# 7segement4digits1badidea-many-digits-mk-.net
KiCad netlist of a schematic drawn in EAGLE
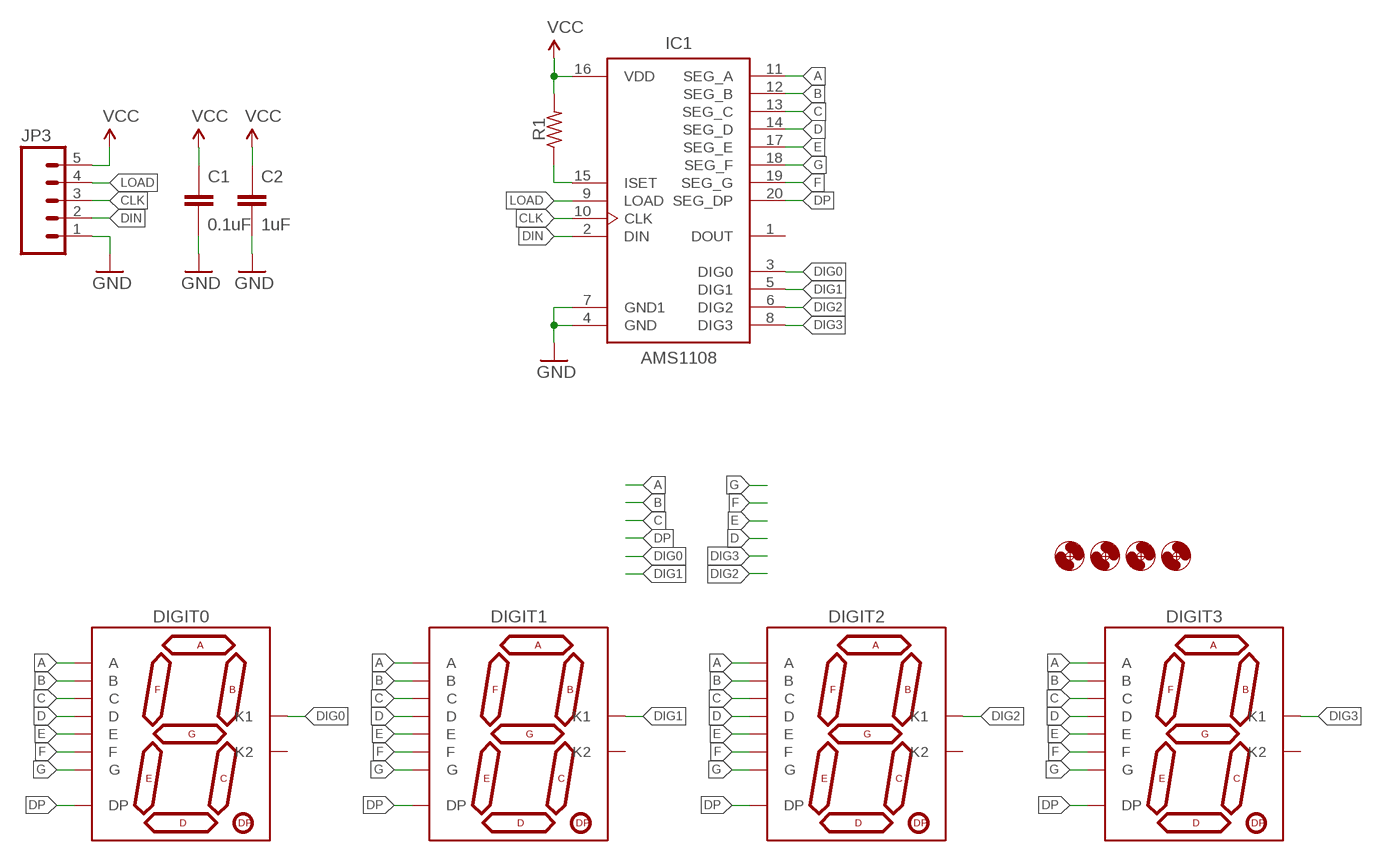
[diagram p0: schematic, sheet 1]

(export (version "E")
  (design (tool "Eeschema 10.0.6"))
  (components
    (comp (ref "C1")
      (value "0.1uF")
      (footprint "eagle-import:C0603")
      (libsource (lib "eagle-import") (part "CAPACITOR-CERAMICC0603"))
    )
    (comp (ref "C2")
      (value "1uF")
      (footprint "eagle-import:C0805")
      (libsource (lib "eagle-import") (part "CAPACITOR-CERAMICC0805"))
    )
    (comp (ref "DIGIT0")
      (value "7SEG_1DIGPTH-25.4MM")
      (footprint "eagle-import:7SEG_1DIG_25.4MM")
      (libsource (lib "eagle-import") (part "7SEG_1DIGPTH-25.4MM"))
    )
    (comp (ref "DIGIT1")
      (value "7SEG_1DIGPTH-25.4MM")
      (footprint "eagle-import:7SEG_1DIG_25.4MM")
      (libsource (lib "eagle-import") (part "7SEG_1DIGPTH-25.4MM"))
    )
    (comp (ref "DIGIT2")
      (value "7SEG_1DIGPTH-25.4MM")
      (footprint "eagle-import:7SEG_1DIG_25.4MM")
      (libsource (lib "eagle-import") (part "7SEG_1DIGPTH-25.4MM"))
    )
    (comp (ref "DIGIT3")
      (value "7SEG_1DIGPTH-25.4MM")
      (footprint "eagle-import:7SEG_1DIG_25.4MM")
      (libsource (lib "eagle-import") (part "7SEG_1DIGPTH-25.4MM"))
    )
    (comp (ref "H1")
      (value "HOLE#2")
      (footprint "eagle-import:HOLE-#2")
      (libsource (lib "eagle-import") (part "HOLE#2"))
    )
    (comp (ref "H2")
      (value "HOLE#2")
      (footprint "eagle-import:HOLE-#2")
      (libsource (lib "eagle-import") (part "HOLE#2"))
    )
    (comp (ref "H3")
      (value "HOLE#2")
      (footprint "eagle-import:HOLE-#2")
      (libsource (lib "eagle-import") (part "HOLE#2"))
    )
    (comp (ref "H4")
      (value "HOLE#2")
      (footprint "eagle-import:HOLE-#2")
      (libsource (lib "eagle-import") (part "HOLE#2"))
    )
    (comp (ref "IC1")
      (value "AMS1108")
      (footprint "eagle-import:SO20W-NOSUCK")
      (libsource (lib "eagle-import") (part "AMS1108SOIC-20W"))
    )
    (comp (ref "JP3")
      (value "M05PTH")
      (footprint "eagle-import:1X05")
      (libsource (lib "eagle-import") (part "M05PTH"))
    )
    (comp (ref "R1")
      (value "RESISTORR0603")
      (footprint "eagle-import:R0603")
      (libsource (lib "eagle-import") (part "RESISTORR0603"))
    )
  )
  (nets
    (net (code "1") (name "A") (class "Default")
      (node (ref "DIGIT0") (pin "7") (pinfunction "A_7") (pintype "bidirectional"))
      (node (ref "DIGIT1") (pin "7") (pinfunction "A_7") (pintype "bidirectional"))
      (node (ref "DIGIT2") (pin "7") (pinfunction "A_7") (pintype "bidirectional"))
      (node (ref "DIGIT3") (pin "7") (pinfunction "A_7") (pintype "bidirectional"))
      (node (ref "IC1") (pin "11") (pinfunction "SEG_A_11") (pintype "bidirectional"))
    )
    (net (code "2") (name "B") (class "Default")
      (node (ref "DIGIT0") (pin "6") (pinfunction "B_6") (pintype "bidirectional"))
      (node (ref "DIGIT1") (pin "6") (pinfunction "B_6") (pintype "bidirectional"))
      (node (ref "DIGIT2") (pin "6") (pinfunction "B_6") (pintype "bidirectional"))
      (node (ref "DIGIT3") (pin "6") (pinfunction "B_6") (pintype "bidirectional"))
      (node (ref "IC1") (pin "12") (pinfunction "SEG_B_12") (pintype "bidirectional"))
    )
    (net (code "3") (name "C") (class "Default")
      (node (ref "DIGIT0") (pin "4") (pinfunction "C_4") (pintype "bidirectional"))
      (node (ref "DIGIT1") (pin "4") (pinfunction "C_4") (pintype "bidirectional"))
      (node (ref "DIGIT2") (pin "4") (pinfunction "C_4") (pintype "bidirectional"))
      (node (ref "DIGIT3") (pin "4") (pinfunction "C_4") (pintype "bidirectional"))
      (node (ref "IC1") (pin "13") (pinfunction "SEG_C_13") (pintype "bidirectional"))
    )
    (net (code "4") (name "CLK") (class "Default")
      (node (ref "IC1") (pin "10") (pinfunction "CLK_10") (pintype "bidirectional"))
      (node (ref "JP3") (pin "3") (pinfunction "3_3") (pintype "passive"))
    )
    (net (code "5") (name "D") (class "Default")
      (node (ref "DIGIT0") (pin "2") (pinfunction "D_2") (pintype "bidirectional"))
      (node (ref "DIGIT1") (pin "2") (pinfunction "D_2") (pintype "bidirectional"))
      (node (ref "DIGIT2") (pin "2") (pinfunction "D_2") (pintype "bidirectional"))
      (node (ref "DIGIT3") (pin "2") (pinfunction "D_2") (pintype "bidirectional"))
      (node (ref "IC1") (pin "14") (pinfunction "SEG_D_14") (pintype "bidirectional"))
    )
    (net (code "6") (name "DIG0") (class "Default")
      (node (ref "DIGIT0") (pin "3") (pinfunction "K1_3") (pintype "bidirectional"))
      (node (ref "IC1") (pin "3") (pinfunction "DIG0_3") (pintype "bidirectional"))
    )
    (net (code "7") (name "DIG1") (class "Default")
      (node (ref "DIGIT1") (pin "3") (pinfunction "K1_3") (pintype "bidirectional"))
      (node (ref "IC1") (pin "5") (pinfunction "DIG1_5") (pintype "bidirectional"))
    )
    (net (code "8") (name "DIG2") (class "Default")
      (node (ref "DIGIT2") (pin "3") (pinfunction "K1_3") (pintype "bidirectional"))
      (node (ref "IC1") (pin "6") (pinfunction "DIG2_6") (pintype "bidirectional"))
    )
    (net (code "9") (name "DIG3") (class "Default")
      (node (ref "DIGIT3") (pin "3") (pinfunction "K1_3") (pintype "bidirectional"))
      (node (ref "IC1") (pin "8") (pinfunction "DIG3_8") (pintype "bidirectional"))
    )
    (net (code "10") (name "DIN") (class "Default")
      (node (ref "IC1") (pin "2") (pinfunction "DIN_2") (pintype "bidirectional"))
      (node (ref "JP3") (pin "2") (pinfunction "2_2") (pintype "passive"))
    )
    (net (code "11") (name "DP") (class "Default")
      (node (ref "DIGIT0") (pin "5") (pinfunction "DP_5") (pintype "bidirectional"))
      (node (ref "DIGIT1") (pin "5") (pinfunction "DP_5") (pintype "bidirectional"))
      (node (ref "DIGIT2") (pin "5") (pinfunction "DP_5") (pintype "bidirectional"))
      (node (ref "DIGIT3") (pin "5") (pinfunction "DP_5") (pintype "bidirectional"))
      (node (ref "IC1") (pin "20") (pinfunction "SEG_DP_20") (pintype "bidirectional"))
    )
    (net (code "12") (name "E") (class "Default")
      (node (ref "DIGIT0") (pin "1") (pinfunction "E_1") (pintype "bidirectional"))
      (node (ref "DIGIT1") (pin "1") (pinfunction "E_1") (pintype "bidirectional"))
      (node (ref "DIGIT2") (pin "1") (pinfunction "E_1") (pintype "bidirectional"))
      (node (ref "DIGIT3") (pin "1") (pinfunction "E_1") (pintype "bidirectional"))
      (node (ref "IC1") (pin "17") (pinfunction "SEG_E_17") (pintype "bidirectional"))
    )
    (net (code "13") (name "F") (class "Default")
      (node (ref "DIGIT0") (pin "9") (pinfunction "F_9") (pintype "bidirectional"))
      (node (ref "DIGIT1") (pin "9") (pinfunction "F_9") (pintype "bidirectional"))
      (node (ref "DIGIT2") (pin "9") (pinfunction "F_9") (pintype "bidirectional"))
      (node (ref "DIGIT3") (pin "9") (pinfunction "F_9") (pintype "bidirectional"))
      (node (ref "IC1") (pin "19") (pinfunction "SEG_G_19") (pintype "bidirectional"))
    )
    (net (code "14") (name "G") (class "Default")
      (node (ref "DIGIT0") (pin "10") (pinfunction "G_10") (pintype "bidirectional"))
      (node (ref "DIGIT1") (pin "10") (pinfunction "G_10") (pintype "bidirectional"))
      (node (ref "DIGIT2") (pin "10") (pinfunction "G_10") (pintype "bidirectional"))
      (node (ref "DIGIT3") (pin "10") (pinfunction "G_10") (pintype "bidirectional"))
      (node (ref "IC1") (pin "18") (pinfunction "SEG_F_18") (pintype "bidirectional"))
    )
    (net (code "15") (name "GND") (class "Default")
      (node (ref "C1") (pin "2") (pinfunction "2_2") (pintype "passive"))
      (node (ref "C2") (pin "2") (pinfunction "2_2") (pintype "passive"))
      (node (ref "IC1") (pin "4") (pinfunction "GND_4") (pintype "bidirectional"))
      (node (ref "IC1") (pin "7") (pinfunction "GND1_7") (pintype "bidirectional"))
      (node (ref "JP3") (pin "1") (pinfunction "1_1") (pintype "passive"))
    )
    (net (code "16") (name "LOAD") (class "Default")
      (node (ref "IC1") (pin "9") (pinfunction "LOAD_9") (pintype "bidirectional"))
      (node (ref "JP3") (pin "4") (pinfunction "4_4") (pintype "passive"))
    )
    (net (code "17") (name "Net-(IC1-ISET)") (class "Default")
      (node (ref "IC1") (pin "15") (pinfunction "ISET_15") (pintype "bidirectional"))
      (node (ref "R1") (pin "1") (pinfunction "1_1") (pintype "passive"))
    )
    (net (code "18") (name "VCC") (class "Default")
      (node (ref "C1") (pin "1") (pinfunction "1_1") (pintype "passive"))
      (node (ref "C2") (pin "1") (pinfunction "1_1") (pintype "passive"))
      (node (ref "IC1") (pin "16") (pinfunction "VDD_16") (pintype "bidirectional"))
      (node (ref "JP3") (pin "5") (pinfunction "5_5") (pintype "passive"))
      (node (ref "R1") (pin "2") (pinfunction "2_2") (pintype "passive"))
    )
    (net (code "19") (name "unconnected-(DIGIT0-K2-Pad8)") (class "Default")
      (node (ref "DIGIT0") (pin "8") (pinfunction "K2_8") (pintype "bidirectional"))
    )
    (net (code "20") (name "unconnected-(DIGIT1-K2-Pad8)") (class "Default")
      (node (ref "DIGIT1") (pin "8") (pinfunction "K2_8") (pintype "bidirectional"))
    )
    (net (code "21") (name "unconnected-(DIGIT2-K2-Pad8)") (class "Default")
      (node (ref "DIGIT2") (pin "8") (pinfunction "K2_8") (pintype "bidirectional"))
    )
    (net (code "22") (name "unconnected-(DIGIT3-K2-Pad8)") (class "Default")
      (node (ref "DIGIT3") (pin "8") (pinfunction "K2_8") (pintype "bidirectional"))
    )
    (net (code "23") (name "unconnected-(IC1-DOUT-Pad1)") (class "Default")
      (node (ref "IC1") (pin "1") (pinfunction "DOUT_1") (pintype "bidirectional"))
    )
  )
)
